# HC05-mdl_V04.net
KiCad netlist of a schematic drawn in EAGLE
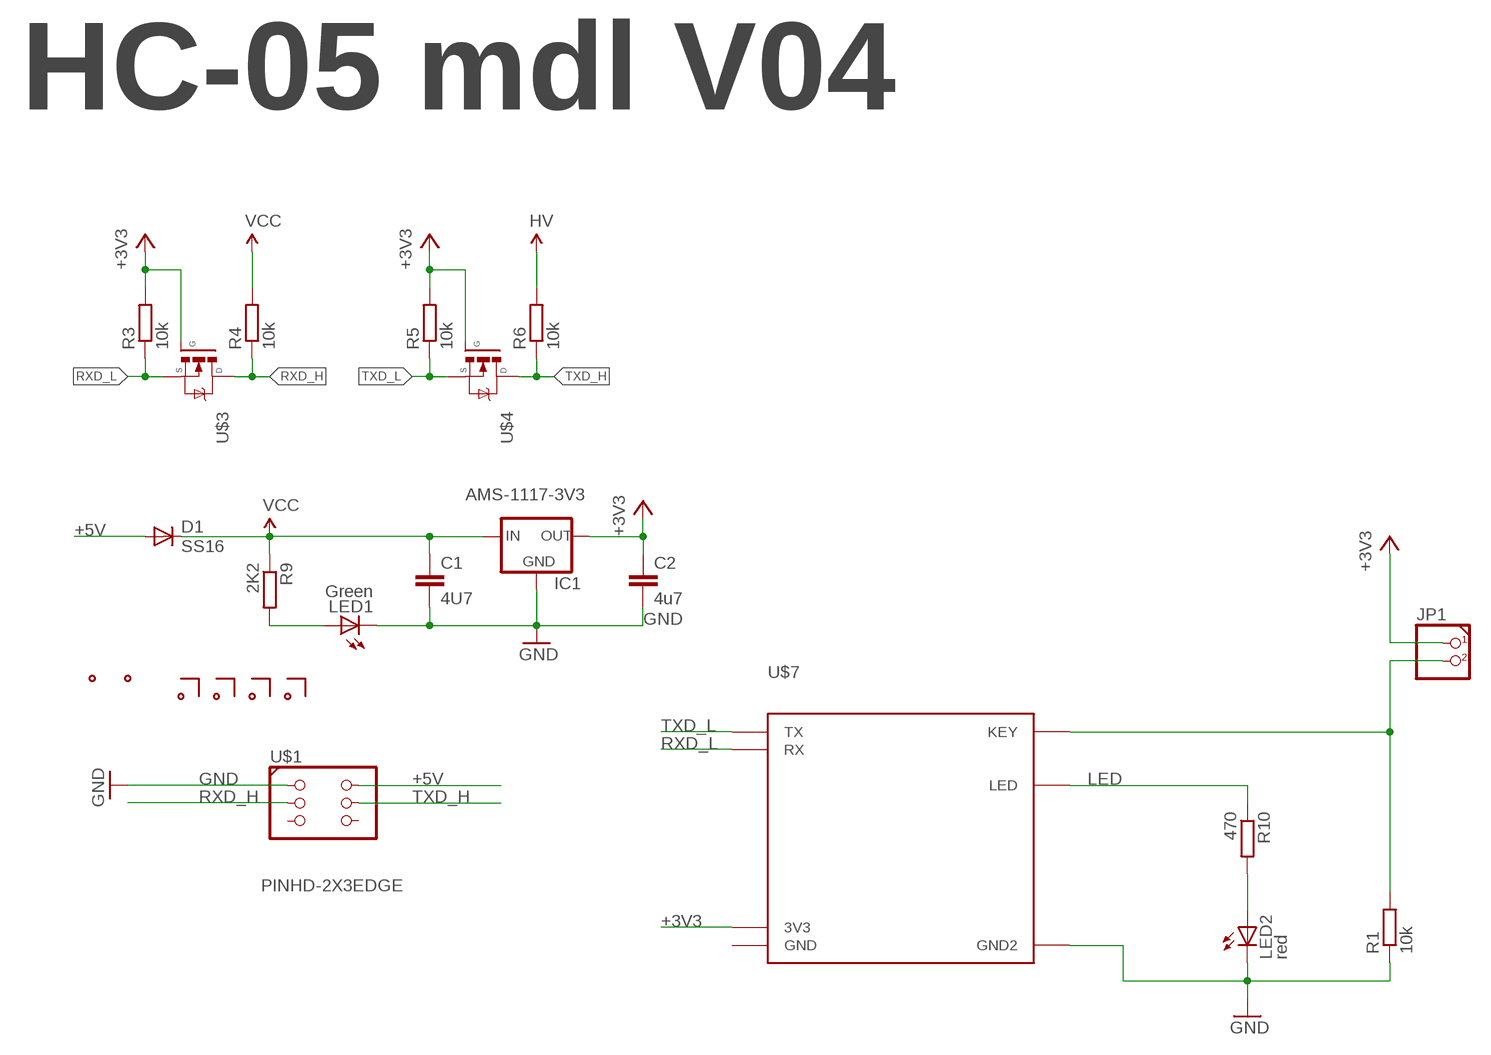
[diagram p0: schematic, sheet 1]

(export (version "E")
  (design (tool "Eeschema 10.0.6"))
  (components
    (comp (ref "C1")
      (value "4U7")
      (footprint "eagle-import:C0805")
      (libsource (lib "eagle-import") (part "C-EUC0805"))
    )
    (comp (ref "C2")
      (value "4u7")
      (footprint "eagle-import:C0805")
      (libsource (lib "eagle-import") (part "C-EUC0805"))
    )
    (comp (ref "D1")
      (value "SS16")
      (footprint "eagle-import:DO214AC")
      (libsource (lib "eagle-import") (part "DIODE-DO214AC"))
    )
    (comp (ref "IC1")
      (value "AMS-1117-3V3")
      (footprint "eagle-import:SOT223")
      (libsource (lib "eagle-import") (part "LM1117"))
    )
    (comp (ref "JP1")
      (value "PINHD-1X2")
      (footprint "eagle-import:1X02")
      (libsource (lib "eagle-import") (part "PINHD-1X2"))
    )
    (comp (ref "LED1")
      (value "Green")
      (footprint "eagle-import:CHIPLED_1206")
      (libsource (lib "eagle-import") (part "LEDCHIPLED_1206"))
    )
    (comp (ref "LED2")
      (value "red")
      (footprint "eagle-import:CHIPLED_1206")
      (libsource (lib "eagle-import") (part "LEDCHIPLED_1206"))
    )
    (comp (ref "R1")
      (value "10k")
      (footprint "eagle-import:R0805")
      (libsource (lib "eagle-import") (part "R-EU_R0805"))
    )
    (comp (ref "R3")
      (value "10k")
      (footprint "eagle-import:R0805")
      (libsource (lib "eagle-import") (part "R-EU_R0805"))
    )
    (comp (ref "R4")
      (value "10k")
      (footprint "eagle-import:R0805")
      (libsource (lib "eagle-import") (part "R-EU_R0805"))
    )
    (comp (ref "R5")
      (value "10k")
      (footprint "eagle-import:R0805")
      (libsource (lib "eagle-import") (part "R-EU_R0805"))
    )
    (comp (ref "R6")
      (value "10k")
      (footprint "eagle-import:R0805")
      (libsource (lib "eagle-import") (part "R-EU_R0805"))
    )
    (comp (ref "R9")
      (value "2K2")
      (footprint "eagle-import:R0805")
      (libsource (lib "eagle-import") (part "R-EU_R0805"))
    )
    (comp (ref "R10")
      (value "470")
      (footprint "eagle-import:R0805")
      (libsource (lib "eagle-import") (part "R-EU_R0805"))
    )
    (comp (ref "U$1")
      (value "PINHD-2X3EDGE")
      (footprint "eagle-import:2X03EDGE")
      (libsource (lib "eagle-import") (part "PINHD-2X3EDGE"))
    )
    (comp (ref "U$2")
      (value "MARKER")
      (footprint "eagle-import:MARKER")
      (libsource (lib "eagle-import") (part "MARKER"))
    )
    (comp (ref "U$3")
      (value "2N7002-S")
      (footprint "eagle-import:SOT23-FET-SMALL")
      (libsource (lib "eagle-import") (part "2N7002-S"))
    )
    (comp (ref "U$4")
      (value "2N7002-S")
      (footprint "eagle-import:SOT23-FET-SMALL")
      (libsource (lib "eagle-import") (part "2N7002-S"))
    )
    (comp (ref "U$5")
      (value "MARKER")
      (footprint "eagle-import:MARKER")
      (libsource (lib "eagle-import") (part "MARKER"))
    )
    (comp (ref "U$6")
      (value "MARKERDUAL-60")
      (footprint "eagle-import:MARKER60")
      (libsource (lib "eagle-import") (part "MARKERDUAL-60"))
    )
    (comp (ref "U$7")
      (value "HC-05-MIN")
      (footprint "eagle-import:HC-05-MIN-SMD")
      (libsource (lib "eagle-import") (part "HC-05-MIN"))
    )
    (comp (ref "U$8")
      (value "MARKER")
      (footprint "eagle-import:MARKER")
      (libsource (lib "eagle-import") (part "MARKER"))
    )
    (comp (ref "U$9")
      (value "MARKER")
      (footprint "eagle-import:MARKER")
      (libsource (lib "eagle-import") (part "MARKER"))
    )
  )
  (nets
    (net (code "1") (name "+3V3") (class "Default")
      (node (ref "C2") (pin "1") (pinfunction "1_1") (pintype "passive"))
      (node (ref "IC1") (pin "2") (pinfunction "OUT_2") (pintype "passive"))
      (node (ref "IC1") (pin "4") (pinfunction "OUT_4") (pintype "passive"))
      (node (ref "JP1") (pin "1") (pinfunction "1_1") (pintype "passive"))
      (node (ref "R3") (pin "2") (pinfunction "2_2") (pintype "passive"))
      (node (ref "R5") (pin "2") (pinfunction "2_2") (pintype "passive"))
      (node (ref "U$3") (pin "G") (pinfunction "G_G") (pintype "passive"))
      (node (ref "U$4") (pin "G") (pinfunction "G_G") (pintype "passive"))
      (node (ref "U$7") (pin "3V3") (pinfunction "3V3_3V3") (pintype "bidirectional"))
    )
    (net (code "2") (name "/+5V") (class "Default")
      (node (ref "D1") (pin "A") (pinfunction "A_A") (pintype "passive"))
      (node (ref "U$1") (pin "P$2") (pinfunction "2_P$2") (pintype "passive"))
    )
    (net (code "3") (name "/LED") (class "Default")
      (node (ref "R10") (pin "1") (pinfunction "1_1") (pintype "passive"))
      (node (ref "U$7") (pin "LED") (pinfunction "LED_LED") (pintype "bidirectional"))
    )
    (net (code "4") (name "GND") (class "Default")
      (node (ref "C1") (pin "2") (pinfunction "2_2") (pintype "passive"))
      (node (ref "C2") (pin "2") (pinfunction "2_2") (pintype "passive"))
      (node (ref "IC1") (pin "1") (pinfunction "GND_1") (pintype "input"))
      (node (ref "LED1") (pin "C") (pinfunction "C_C") (pintype "passive"))
      (node (ref "LED2") (pin "C") (pinfunction "C_C") (pintype "passive"))
      (node (ref "R1") (pin "1") (pinfunction "1_1") (pintype "passive"))
      (node (ref "U$1") (pin "P$1") (pinfunction "1_P$1") (pintype "passive"))
      (node (ref "U$7") (pin "GND2") (pinfunction "GND2_GND2") (pintype "bidirectional"))
    )
    (net (code "5") (name "HV") (class "Default")
      (node (ref "C1") (pin "1") (pinfunction "1_1") (pintype "passive"))
      (node (ref "D1") (pin "C") (pinfunction "C_C") (pintype "passive"))
      (node (ref "IC1") (pin "3") (pinfunction "IN_3") (pintype "input"))
      (node (ref "R4") (pin "2") (pinfunction "2_2") (pintype "passive"))
      (node (ref "R6") (pin "2") (pinfunction "2_2") (pintype "passive"))
      (node (ref "R9") (pin "1") (pinfunction "1_1") (pintype "passive"))
    )
    (net (code "6") (name "Net-(JP1-Pad2)") (class "Default")
      (node (ref "JP1") (pin "2") (pinfunction "2_2") (pintype "passive"))
      (node (ref "R1") (pin "2") (pinfunction "2_2") (pintype "passive"))
      (node (ref "U$7") (pin "KEY") (pinfunction "KEY_KEY") (pintype "bidirectional"))
    )
    (net (code "7") (name "Net-(LED1-PadA)") (class "Default")
      (node (ref "LED1") (pin "A") (pinfunction "A_A") (pintype "passive"))
      (node (ref "R9") (pin "2") (pinfunction "2_2") (pintype "passive"))
    )
    (net (code "8") (name "Net-(LED2-PadA)") (class "Default")
      (node (ref "LED2") (pin "A") (pinfunction "A_A") (pintype "passive"))
      (node (ref "R10") (pin "2") (pinfunction "2_2") (pintype "passive"))
    )
    (net (code "9") (name "RXD_H") (class "Default")
      (node (ref "R4") (pin "1") (pinfunction "1_1") (pintype "passive"))
      (node (ref "U$1") (pin "P$3") (pinfunction "3_P$3") (pintype "passive"))
      (node (ref "U$3") (pin "D") (pinfunction "D_D") (pintype "passive"))
    )
    (net (code "10") (name "RXD_L") (class "Default")
      (node (ref "R3") (pin "1") (pinfunction "1_1") (pintype "passive"))
      (node (ref "U$3") (pin "S") (pinfunction "S_S") (pintype "passive"))
      (node (ref "U$7") (pin "RX") (pinfunction "RX_RX") (pintype "bidirectional"))
    )
    (net (code "11") (name "TXD_H") (class "Default")
      (node (ref "R6") (pin "1") (pinfunction "1_1") (pintype "passive"))
      (node (ref "U$1") (pin "P$4") (pinfunction "4_P$4") (pintype "passive"))
      (node (ref "U$4") (pin "D") (pinfunction "D_D") (pintype "passive"))
    )
    (net (code "12") (name "TXD_L") (class "Default")
      (node (ref "R5") (pin "1") (pinfunction "1_1") (pintype "passive"))
      (node (ref "U$4") (pin "S") (pinfunction "S_S") (pintype "passive"))
      (node (ref "U$7") (pin "TX") (pinfunction "TX_TX") (pintype "bidirectional"))
    )
    (net (code "13") (name "unconnected-(U$1-5-PadP$5)") (class "Default")
      (node (ref "U$1") (pin "P$5") (pinfunction "5_P$5") (pintype "passive"))
    )
    (net (code "14") (name "unconnected-(U$1-6-PadP$6)") (class "Default")
      (node (ref "U$1") (pin "P$6") (pinfunction "6_P$6") (pintype "passive"))
    )
    (net (code "15") (name "unconnected-(U$7-PadGND)") (class "Default")
      (node (ref "U$7") (pin "GND") (pinfunction "GND_GND") (pintype "bidirectional"))
    )
  )
)
